# EV_Display_Schematic.net
KiCad netlist of a schematic drawn in EAGLE
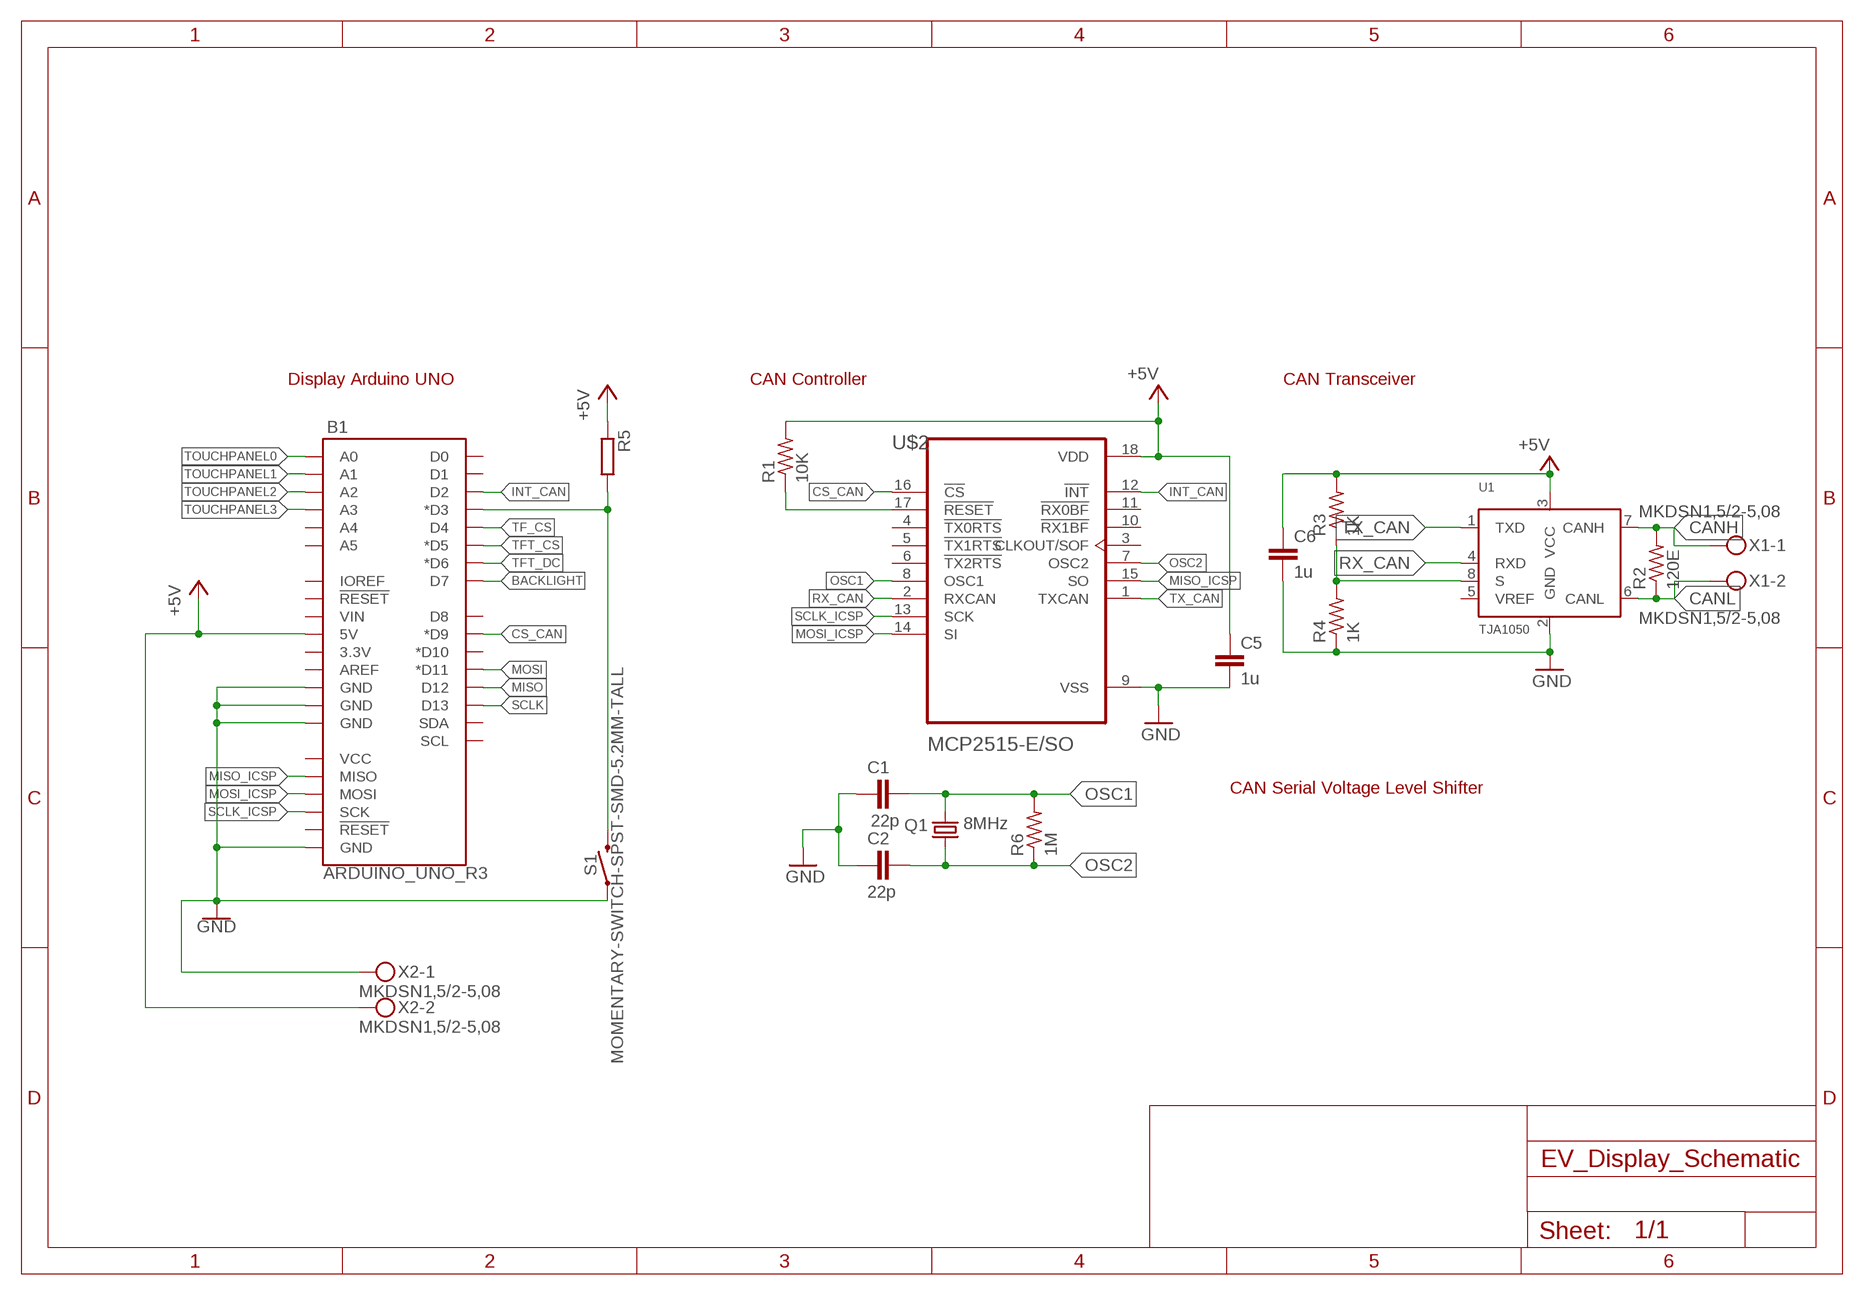
[diagram p0: schematic, sheet 1]

(export (version "E")
  (design (tool "Eeschema 10.0.6"))
  (components
    (comp (ref "B1")
      (value "ARDUINO_UNO_R3")
      (footprint "eagle-import:ARDUINO_R3")
      (libsource (lib "eagle-import") (part "ARDUINO_UNO_R3"))
    )
    (comp (ref "C1")
      (value "22p")
      (footprint "eagle-import:C0805")
      (libsource (lib "eagle-import") (part "C-EUC0805"))
    )
    (comp (ref "C2")
      (value "22p")
      (footprint "eagle-import:C0805")
      (libsource (lib "eagle-import") (part "C-EUC0805"))
    )
    (comp (ref "C5")
      (value "1u")
      (footprint "eagle-import:C0805")
      (libsource (lib "eagle-import") (part "C-EUC0805"))
    )
    (comp (ref "C6")
      (value "1u")
      (footprint "eagle-import:C0805")
      (libsource (lib "eagle-import") (part "C-EUC0805"))
    )
    (comp (ref "Q1")
      (value "8MHz")
      (footprint "eagle-import:HC49_S")
      (libsource (lib "eagle-import") (part "CRYSTALHC49S"))
    )
    (comp (ref "R1")
      (value "10K")
      (footprint "eagle-import:R0805")
      (libsource (lib "eagle-import") (part "R-US_R0805"))
    )
    (comp (ref "R2")
      (value "120E")
      (footprint "eagle-import:R0805")
      (libsource (lib "eagle-import") (part "R-US_R0805"))
    )
    (comp (ref "R3")
      (value "1K")
      (footprint "eagle-import:R0805")
      (libsource (lib "eagle-import") (part "R-US_R0805"))
    )
    (comp (ref "R4")
      (value "1K")
      (footprint "eagle-import:R0805")
      (libsource (lib "eagle-import") (part "R-US_R0805"))
    )
    (comp (ref "R5")
      (value "R-EU_R0805")
      (footprint "eagle-import:R0805")
      (libsource (lib "eagle-import") (part "R-EU_R0805"))
    )
    (comp (ref "R6")
      (value "1M")
      (footprint "eagle-import:R0805")
      (libsource (lib "eagle-import") (part "R-US_R0805"))
    )
    (comp (ref "S1")
      (value "MOMENTARY-SWITCH-SPST-SMD-5.2MM-TALL")
      (footprint "eagle-import:TACTILE_SWITCH_SMD_5.2MM")
      (libsource (lib "eagle-import") (part "MOMENTARY-SWITCH-SPST-SMD-5.2MM-TALL"))
    )
    (comp (ref "U$2")
      (value "MCP2515-E/SO")
      (footprint "eagle-import:SOIC127P1030X265-18N")
      (fields (field (name "MF") "Microchip"))
      (libsource (lib "eagle-import") (part "MCP2515-E/SO"))
    )
    (comp (ref "U1")
      (value "TJA1050")
      (footprint "eagle-import:SOT96-1")
      (fields (field (name "MF") "NXP USA"))
      (libsource (lib "eagle-import") (part "TJA1050"))
    )
    (comp (ref "X1")
      (value "MKDSN1,5/2-5,08")
      (footprint "eagle-import:MKDSN1,5_2-5,08")
      (libsource (lib "eagle-import") (part "MKDSN1,5/2-5,08"))
    )
    (comp (ref "X2")
      (value "MKDSN1,5/2-5,08")
      (footprint "eagle-import:MKDSN1,5_2-5,08")
      (libsource (lib "eagle-import") (part "MKDSN1,5/2-5,08"))
    )
  )
  (nets
    (net (code "1") (name "+5V") (class "Default")
      (node (ref "B1") (pin "5V") (pinfunction "5V_5V") (pintype "bidirectional"))
      (node (ref "C5") (pin "1") (pinfunction "1_1") (pintype "passive"))
      (node (ref "C6") (pin "1") (pinfunction "1_1") (pintype "passive"))
      (node (ref "R1") (pin "2") (pinfunction "2_2") (pintype "passive"))
      (node (ref "R3") (pin "2") (pinfunction "2_2") (pintype "passive"))
      (node (ref "R5") (pin "1") (pinfunction "1_1") (pintype "passive"))
      (node (ref "U$2") (pin "18") (pinfunction "VDD_18") (pintype "power_in"))
      (node (ref "U1") (pin "3") (pinfunction "VCC_3") (pintype "bidirectional"))
      (node (ref "X2") (pin "2") (pinfunction "KL_2") (pintype "passive"))
    )
    (net (code "2") (name "BACKLIGHT") (class "Default")
      (node (ref "B1") (pin "D7") (pinfunction "D7_D7") (pintype "bidirectional"))
    )
    (net (code "3") (name "CANH") (class "Default")
      (node (ref "R2") (pin "2") (pinfunction "2_2") (pintype "passive"))
      (node (ref "U1") (pin "7") (pinfunction "CANH_7") (pintype "bidirectional"))
      (node (ref "X1") (pin "1") (pinfunction "KL_1") (pintype "passive"))
    )
    (net (code "4") (name "CANL") (class "Default")
      (node (ref "R2") (pin "1") (pinfunction "1_1") (pintype "passive"))
      (node (ref "U1") (pin "6") (pinfunction "CANL_6") (pintype "bidirectional"))
      (node (ref "X1") (pin "2") (pinfunction "KL_2") (pintype "passive"))
    )
    (net (code "5") (name "CS_CAN") (class "Default")
      (node (ref "B1") (pin "D9") (pinfunction "*D9_D9") (pintype "bidirectional"))
      (node (ref "U$2") (pin "16") (pinfunction "~{CS}_16") (pintype "input"))
    )
    (net (code "6") (name "GND") (class "Default")
      (node (ref "B1") (pin "GND@1") (pinfunction "GND_GND@1") (pintype "bidirectional"))
      (node (ref "B1") (pin "GND@2") (pinfunction "GND_GND@2") (pintype "bidirectional"))
      (node (ref "B1") (pin "GND@3") (pinfunction "GND_GND@3") (pintype "bidirectional"))
      (node (ref "B1") (pin "GND@4") (pinfunction "GND_GND@4") (pintype "bidirectional"))
      (node (ref "C1") (pin "1") (pinfunction "1_1") (pintype "passive"))
      (node (ref "C2") (pin "1") (pinfunction "1_1") (pintype "passive"))
      (node (ref "C5") (pin "2") (pinfunction "2_2") (pintype "passive"))
      (node (ref "C6") (pin "2") (pinfunction "2_2") (pintype "passive"))
      (node (ref "R4") (pin "1") (pinfunction "1_1") (pintype "passive"))
      (node (ref "S1") (pin "1") (pinfunction "1_1") (pintype "passive"))
      (node (ref "U$2") (pin "9") (pinfunction "VSS_9") (pintype "power_in"))
      (node (ref "U1") (pin "2") (pinfunction "GND_2") (pintype "bidirectional"))
      (node (ref "X2") (pin "1") (pinfunction "KL_1") (pintype "passive"))
    )
    (net (code "7") (name "INT_CAN") (class "Default")
      (node (ref "B1") (pin "D2") (pinfunction "D2_D2") (pintype "bidirectional"))
      (node (ref "U$2") (pin "12") (pinfunction "~{INT}_12") (pintype "output"))
    )
    (net (code "8") (name "MISO") (class "Default")
      (node (ref "B1") (pin "D12") (pinfunction "D12_D12") (pintype "bidirectional"))
    )
    (net (code "9") (name "MISO_ICSP") (class "Default")
      (node (ref "B1") (pin "MISO") (pinfunction "MISO_MISO") (pintype "bidirectional"))
      (node (ref "U$2") (pin "15") (pinfunction "SO_15") (pintype "output"))
    )
    (net (code "10") (name "MOSI") (class "Default")
      (node (ref "B1") (pin "D11") (pinfunction "*D11_D11") (pintype "bidirectional"))
    )
    (net (code "11") (name "MOSI_ICSP") (class "Default")
      (node (ref "B1") (pin "MOSI") (pinfunction "MOSI_MOSI") (pintype "bidirectional"))
      (node (ref "U$2") (pin "14") (pinfunction "SI_14") (pintype "input"))
    )
    (net (code "12") (name "Net-(B1-*D3)") (class "Default")
      (node (ref "B1") (pin "D3") (pinfunction "*D3_D3") (pintype "bidirectional"))
      (node (ref "R5") (pin "2") (pinfunction "2_2") (pintype "passive"))
      (node (ref "S1") (pin "3") (pinfunction "2_3") (pintype "passive"))
    )
    (net (code "13") (name "Net-(U$2-~{RESET})") (class "Default")
      (node (ref "R1") (pin "1") (pinfunction "1_1") (pintype "passive"))
      (node (ref "U$2") (pin "17") (pinfunction "~{RESET}_17") (pintype "input"))
    )
    (net (code "14") (name "Net-(U1-S)") (class "Default")
      (node (ref "R3") (pin "1") (pinfunction "1_1") (pintype "passive"))
      (node (ref "R4") (pin "2") (pinfunction "2_2") (pintype "passive"))
      (node (ref "U1") (pin "8") (pinfunction "S_8") (pintype "power_in"))
    )
    (net (code "15") (name "OSC1") (class "Default")
      (node (ref "C1") (pin "2") (pinfunction "2_2") (pintype "passive"))
      (node (ref "Q1") (pin "2") (pinfunction "2_2") (pintype "passive"))
      (node (ref "R6") (pin "2") (pinfunction "2_2") (pintype "passive"))
      (node (ref "U$2") (pin "8") (pinfunction "OSC1_8") (pintype "input"))
    )
    (net (code "16") (name "OSC2") (class "Default")
      (node (ref "C2") (pin "2") (pinfunction "2_2") (pintype "passive"))
      (node (ref "Q1") (pin "1") (pinfunction "1_1") (pintype "passive"))
      (node (ref "R6") (pin "1") (pinfunction "1_1") (pintype "passive"))
      (node (ref "U$2") (pin "7") (pinfunction "OSC2_7") (pintype "output"))
    )
    (net (code "17") (name "RX_CAN") (class "Default")
      (node (ref "U$2") (pin "2") (pinfunction "RXCAN_2") (pintype "input"))
      (node (ref "U1") (pin "4") (pinfunction "RXD_4") (pintype "bidirectional"))
    )
    (net (code "18") (name "SCLK") (class "Default")
      (node (ref "B1") (pin "D13") (pinfunction "D13_D13") (pintype "bidirectional"))
    )
    (net (code "19") (name "SCLK_ICSP") (class "Default")
      (node (ref "B1") (pin "SCK") (pinfunction "SCK_SCK") (pintype "bidirectional"))
      (node (ref "U$2") (pin "13") (pinfunction "SCK_13") (pintype "input"))
    )
    (net (code "20") (name "TFT_CS") (class "Default")
      (node (ref "B1") (pin "D5") (pinfunction "*D5_D5") (pintype "bidirectional"))
    )
    (net (code "21") (name "TFT_DC") (class "Default")
      (node (ref "B1") (pin "D6") (pinfunction "*D6_D6") (pintype "bidirectional"))
    )
    (net (code "22") (name "TF_CS") (class "Default")
      (node (ref "B1") (pin "D4") (pinfunction "D4_D4") (pintype "bidirectional"))
    )
    (net (code "23") (name "TOUCHPANEL0") (class "Default")
      (node (ref "B1") (pin "A0") (pinfunction "A0_A0") (pintype "bidirectional"))
    )
    (net (code "24") (name "TOUCHPANEL1") (class "Default")
      (node (ref "B1") (pin "A1") (pinfunction "A1_A1") (pintype "bidirectional"))
    )
    (net (code "25") (name "TOUCHPANEL2") (class "Default")
      (node (ref "B1") (pin "A2") (pinfunction "A2_A2") (pintype "bidirectional"))
    )
    (net (code "26") (name "TOUCHPANEL3") (class "Default")
      (node (ref "B1") (pin "A3") (pinfunction "A3_A3") (pintype "bidirectional"))
    )
    (net (code "27") (name "TX_CAN") (class "Default")
      (node (ref "U$2") (pin "1") (pinfunction "TXCAN_1") (pintype "output"))
      (node (ref "U1") (pin "1") (pinfunction "TXD_1") (pintype "output"))
    )
    (net (code "28") (name "unconnected-(B1-*D10-PadD10)") (class "Default")
      (node (ref "B1") (pin "D10") (pinfunction "*D10_D10") (pintype "bidirectional"))
    )
    (net (code "29") (name "unconnected-(B1-Pad3.3V)") (class "Default")
      (node (ref "B1") (pin "3.3V") (pinfunction "3.3V_3.3V") (pintype "bidirectional"))
    )
    (net (code "30") (name "unconnected-(B1-PadA4)") (class "Default")
      (node (ref "B1") (pin "A4") (pinfunction "A4_A4") (pintype "bidirectional"))
    )
    (net (code "31") (name "unconnected-(B1-PadA5)") (class "Default")
      (node (ref "B1") (pin "A5") (pinfunction "A5_A5") (pintype "bidirectional"))
    )
    (net (code "32") (name "unconnected-(B1-PadAREF)") (class "Default")
      (node (ref "B1") (pin "AREF") (pinfunction "AREF_AREF") (pintype "bidirectional"))
    )
    (net (code "33") (name "unconnected-(B1-PadD0)") (class "Default")
      (node (ref "B1") (pin "D0") (pinfunction "D0_D0") (pintype "bidirectional"))
    )
    (net (code "34") (name "unconnected-(B1-PadD1)") (class "Default")
      (node (ref "B1") (pin "D1") (pinfunction "D1_D1") (pintype "bidirectional"))
    )
    (net (code "35") (name "unconnected-(B1-PadD8)") (class "Default")
      (node (ref "B1") (pin "D8") (pinfunction "D8_D8") (pintype "bidirectional"))
    )
    (net (code "36") (name "unconnected-(B1-PadIOREF)") (class "Default")
      (node (ref "B1") (pin "IOREF") (pinfunction "IOREF_IOREF") (pintype "bidirectional"))
    )
    (net (code "37") (name "unconnected-(B1-PadSCL)") (class "Default")
      (node (ref "B1") (pin "SCL") (pinfunction "SCL_SCL") (pintype "bidirectional"))
    )
    (net (code "38") (name "unconnected-(B1-PadSDA)") (class "Default")
      (node (ref "B1") (pin "SDA") (pinfunction "SDA_SDA") (pintype "bidirectional"))
    )
    (net (code "39") (name "unconnected-(B1-PadVCC)") (class "Default")
      (node (ref "B1") (pin "VCC") (pinfunction "VCC_VCC") (pintype "bidirectional"))
    )
    (net (code "40") (name "unconnected-(B1-PadVIN)") (class "Default")
      (node (ref "B1") (pin "VIN") (pinfunction "VIN_VIN") (pintype "bidirectional"))
    )
    (net (code "41") (name "unconnected-(B1-~{RESET}-PadRESET@1)") (class "Default")
      (node (ref "B1") (pin "RESET@1") (pinfunction "~{RESET}_RESET@1") (pintype "bidirectional"))
    )
    (net (code "42") (name "unconnected-(B1-~{RESET}-PadRESET@2)") (class "Default")
      (node (ref "B1") (pin "RESET@2") (pinfunction "~{RESET}_RESET@2") (pintype "bidirectional"))
    )
    (net (code "43") (name "unconnected-(U$2-CLKOUT{slash}SOF-Pad3)") (class "Default")
      (node (ref "U$2") (pin "3") (pinfunction "CLKOUT/SOF_3") (pintype "output"))
    )
    (net (code "44") (name "unconnected-(U$2-~{RX0BF}-Pad11)") (class "Default")
      (node (ref "U$2") (pin "11") (pinfunction "~{RX0BF}_11") (pintype "output"))
    )
    (net (code "45") (name "unconnected-(U$2-~{RX1BF}-Pad10)") (class "Default")
      (node (ref "U$2") (pin "10") (pinfunction "~{RX1BF}_10") (pintype "output"))
    )
    (net (code "46") (name "unconnected-(U$2-~{TX0RTS}-Pad4)") (class "Default")
      (node (ref "U$2") (pin "4") (pinfunction "~{TX0RTS}_4") (pintype "input"))
    )
    (net (code "47") (name "unconnected-(U$2-~{TX1RTS}-Pad5)") (class "Default")
      (node (ref "U$2") (pin "5") (pinfunction "~{TX1RTS}_5") (pintype "input"))
    )
    (net (code "48") (name "unconnected-(U$2-~{TX2RTS}-Pad6)") (class "Default")
      (node (ref "U$2") (pin "6") (pinfunction "~{TX2RTS}_6") (pintype "input"))
    )
    (net (code "49") (name "unconnected-(U1-VREF-Pad5)") (class "Default")
      (node (ref "U1") (pin "5") (pinfunction "VREF_5") (pintype "passive"))
    )
  )
)
